# S7CAS-PLEIADES-CARTE-MERE_P07_FPGA_0.net
KiCad netlist of a schematic drawn in Altium Designer
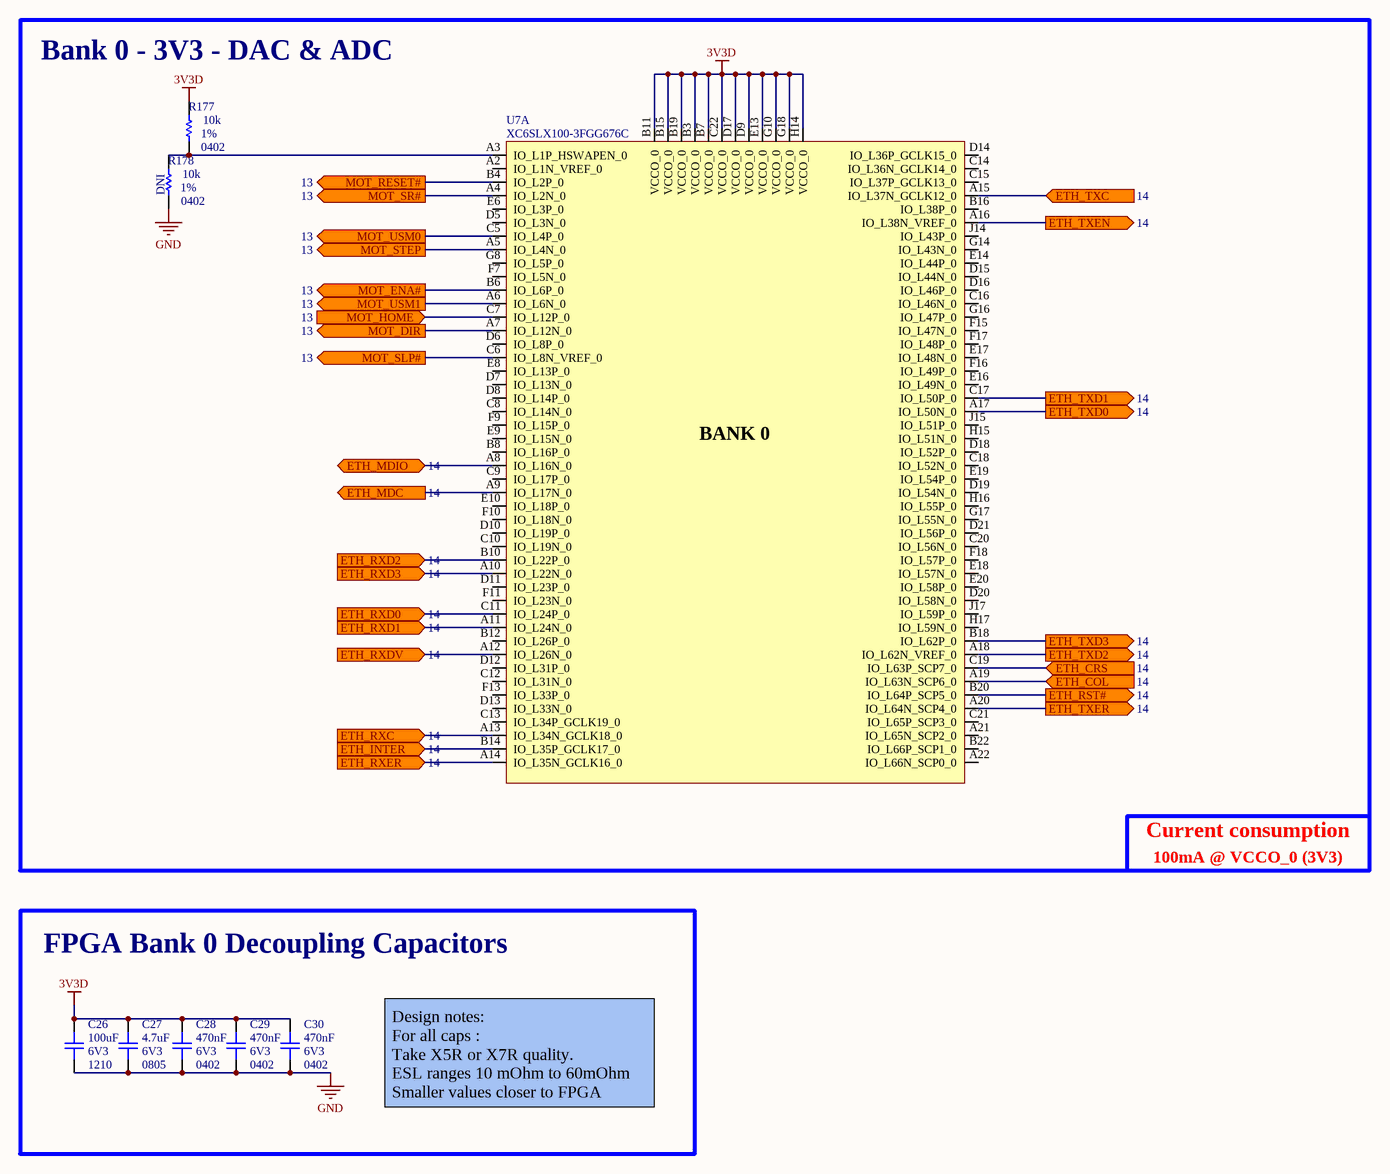
[diagram p0: S7CAS-PLEIADES-CARTE-MERE_P07_FPGA_0.SchDoc]

(export (version "E")
  (design (tool "Eeschema 10.0.6"))
  (components
    (comp (ref "C26")
      (value "100uF")
      (footprint "CAP_1210")
      (description "CAP - 1210")
      (fields
        (field (name "VOLTAGE") "6V3")
        (field (name "PACKAGE") "1210")
        (field (name "CREATEDBY") "Jonathan Bouchard")
      )
      (libsource (lib "S7CAS_LIB2021") (part "CAP - 1210"))
    )
    (comp (ref "C27")
      (value "4.7uF")
      (footprint "CAP_0805")
      (description "CAP - 0805")
      (fields
        (field (name "VOLTAGE") "6V3")
        (field (name "PACKAGE") "0805")
        (field (name "CREATEDBY") "Jonathan Bouchard")
      )
      (libsource (lib "S7CAS_LIB2021") (part "CAP - 0805"))
    )
    (comp (ref "C28")
      (value "470nF")
      (footprint "CAP_0402")
      (description "CAP - 0402")
      (fields
        (field (name "VOLTAGE") "6V3")
        (field (name "PACKAGE") "0402")
        (field (name "CREATEDBY") "Jonathan Bouchard")
      )
      (libsource (lib "S7CAS_LIB2021") (part "CAP - 0402"))
    )
    (comp (ref "C29")
      (value "470nF")
      (footprint "CAP_0402")
      (description "CAP - 0402")
      (fields
        (field (name "VOLTAGE") "6V3")
        (field (name "PACKAGE") "0402")
        (field (name "CREATEDBY") "Jonathan Bouchard")
      )
      (libsource (lib "S7CAS_LIB2021") (part "CAP - 0402"))
    )
    (comp (ref "C30")
      (value "470nF")
      (footprint "CAP_0402")
      (description "CAP - 0402")
      (fields
        (field (name "VOLTAGE") "6V3")
        (field (name "PACKAGE") "0402")
        (field (name "CREATEDBY") "Jonathan Bouchard")
      )
      (libsource (lib "S7CAS_LIB2021") (part "CAP - 0402"))
    )
    (comp (ref "R177")
      (value "10k")
      (footprint "RES_0402")
      (description "RES - 0402")
      (fields
        (field (name "VOLTAGE") "50V")
        (field (name "POWER") "1/16W")
        (field (name "PACKAGE") "0402")
        (field (name "PRECISION") "1%")
        (field (name "CREATEDBY") "Jonathan Bouchard")
      )
      (libsource (lib "S7CAS_LIB2021") (part "RES - 0402"))
    )
    (comp (ref "R178")
      (value "10k")
      (footprint "RES_0402")
      (description "RES - 0402")
      (fields
        (field (name "VOLTAGE") "50V")
        (field (name "POWER") "1/16W")
        (field (name "NI") "DNI")
        (field (name "PACKAGE") "0402")
        (field (name "PRECISION") "1%")
        (field (name "CREATEDBY") "Jonathan Bouchard")
      )
      (libsource (lib "S7CAS_LIB2021") (part "RES - 0402"))
    )
    (comp (ref "U7")
      (value "XC6SLX100-3FGG676C")
      (footprint "FPGA_XILINX_FGG676")
      (description "FPGA - XILINX SPARTAN 6 480 I/O - BGA-676")
      (fields
        (field (name "VOLTAGE") "1.14 V ~ 1.26 V")
        (field (name "MFG") "Xilinx")
        (field (name "CREATEDBY") "Jonathan Bouchard")
      )
      (libsource (lib "S7CAS_LIB2021") (part "FPGA_XC6SLX100-3FGG676C"))
    )
  )
  (nets
    (net (code "1") (name "/ETH_COL") (class "Default")
      (node (ref "U7") (pin "A19") (pinfunction "IO_L63N_SCP6_0_A19") (pintype "passive"))
    )
    (net (code "2") (name "/ETH_CRS") (class "Default")
      (node (ref "U7") (pin "C19") (pinfunction "IO_L63P_SCP7_0_C19") (pintype "passive"))
    )
    (net (code "3") (name "/ETH_INTER") (class "Default")
      (node (ref "U7") (pin "B14") (pinfunction "IO_L35P_GCLK17_0_B14") (pintype "passive"))
    )
    (net (code "4") (name "/ETH_MDC") (class "Default")
      (node (ref "U7") (pin "A9") (pinfunction "IO_L17N_0_A9") (pintype "passive"))
    )
    (net (code "5") (name "/ETH_MDIO") (class "Default")
      (node (ref "U7") (pin "A8") (pinfunction "IO_L16N_0_A8") (pintype "passive"))
    )
    (net (code "6") (name "/ETH_RST#") (class "Default")
      (node (ref "U7") (pin "B20") (pinfunction "IO_L64P_SCP5_0_B20") (pintype "passive"))
    )
    (net (code "7") (name "/ETH_RXC") (class "Default")
      (node (ref "U7") (pin "A13") (pinfunction "IO_L34N_GCLK18_0_A13") (pintype "passive"))
    )
    (net (code "8") (name "/ETH_RXD0") (class "Default")
      (node (ref "U7") (pin "C11") (pinfunction "IO_L24P_0_C11") (pintype "passive"))
    )
    (net (code "9") (name "/ETH_RXD1") (class "Default")
      (node (ref "U7") (pin "A11") (pinfunction "IO_L24N_0_A11") (pintype "passive"))
    )
    (net (code "10") (name "/ETH_RXD2") (class "Default")
      (node (ref "U7") (pin "B10") (pinfunction "IO_L22P_0_B10") (pintype "passive"))
    )
    (net (code "11") (name "/ETH_RXD3") (class "Default")
      (node (ref "U7") (pin "A10") (pinfunction "IO_L22N_0_A10") (pintype "passive"))
    )
    (net (code "12") (name "/ETH_RXDV") (class "Default")
      (node (ref "U7") (pin "A12") (pinfunction "IO_L26N_0_A12") (pintype "passive"))
    )
    (net (code "13") (name "/ETH_RXER") (class "Default")
      (node (ref "U7") (pin "A14") (pinfunction "IO_L35N_GCLK16_0_A14") (pintype "passive"))
    )
    (net (code "14") (name "/ETH_TXC") (class "Default")
      (node (ref "U7") (pin "A15") (pinfunction "IO_L37N_GCLK12_0_A15") (pintype "passive"))
    )
    (net (code "15") (name "/ETH_TXD0") (class "Default")
      (node (ref "U7") (pin "A17") (pinfunction "IO_L50N_0_A17") (pintype "passive"))
    )
    (net (code "16") (name "/ETH_TXD1") (class "Default")
      (node (ref "U7") (pin "C17") (pinfunction "IO_L50P_0_C17") (pintype "passive"))
    )
    (net (code "17") (name "/ETH_TXD2") (class "Default")
      (node (ref "U7") (pin "A18") (pinfunction "IO_L62N_VREF_0_A18") (pintype "passive"))
    )
    (net (code "18") (name "/ETH_TXD3") (class "Default")
      (node (ref "U7") (pin "B18") (pinfunction "IO_L62P_0_B18") (pintype "passive"))
    )
    (net (code "19") (name "/ETH_TXEN") (class "Default")
      (node (ref "U7") (pin "A16") (pinfunction "IO_L38N_VREF_0_A16") (pintype "passive"))
    )
    (net (code "20") (name "/ETH_TXER") (class "Default")
      (node (ref "U7") (pin "A20") (pinfunction "IO_L64N_SCP4_0_A20") (pintype "passive"))
    )
    (net (code "21") (name "/MOT_DIR") (class "Default")
      (node (ref "U7") (pin "A7") (pinfunction "IO_L12N_0_A7") (pintype "passive"))
    )
    (net (code "22") (name "/MOT_ENA#") (class "Default")
      (node (ref "U7") (pin "B6") (pinfunction "IO_L6P_0_B6") (pintype "passive"))
    )
    (net (code "23") (name "/MOT_HOME") (class "Default")
      (node (ref "U7") (pin "C7") (pinfunction "IO_L12P_0_C7") (pintype "passive"))
    )
    (net (code "24") (name "/MOT_RESET#") (class "Default")
      (node (ref "U7") (pin "B4") (pinfunction "IO_L2P_0_B4") (pintype "passive"))
    )
    (net (code "25") (name "/MOT_SLP#") (class "Default")
      (node (ref "U7") (pin "C6") (pinfunction "IO_L8N_VREF_0_C6") (pintype "passive"))
    )
    (net (code "26") (name "/MOT_SR#") (class "Default")
      (node (ref "U7") (pin "A4") (pinfunction "IO_L2N_0_A4") (pintype "passive"))
    )
    (net (code "27") (name "/MOT_STEP") (class "Default")
      (node (ref "U7") (pin "A5") (pinfunction "IO_L4N_0_A5") (pintype "passive"))
    )
    (net (code "28") (name "/MOT_USM0") (class "Default")
      (node (ref "U7") (pin "C5") (pinfunction "IO_L4P_0_C5") (pintype "passive"))
    )
    (net (code "29") (name "/MOT_USM1") (class "Default")
      (node (ref "U7") (pin "A6") (pinfunction "IO_L6N_0_A6") (pintype "passive"))
    )
    (net (code "30") (name "3V3D") (class "Default")
      (node (ref "C26") (pin "2") (pinfunction "2_2") (pintype "passive"))
      (node (ref "C27") (pin "2") (pinfunction "2_2") (pintype "passive"))
      (node (ref "C28") (pin "2") (pinfunction "2_2") (pintype "passive"))
      (node (ref "C29") (pin "2") (pinfunction "2_2") (pintype "passive"))
      (node (ref "C30") (pin "2") (pinfunction "2_2") (pintype "passive"))
      (node (ref "R177") (pin "2") (pinfunction "2_2") (pintype "passive"))
      (node (ref "U7") (pin "B11") (pinfunction "VCCO_0_B11") (pintype "passive"))
      (node (ref "U7") (pin "B15") (pinfunction "VCCO_0_B15") (pintype "passive"))
      (node (ref "U7") (pin "B19") (pinfunction "VCCO_0_B19") (pintype "passive"))
      (node (ref "U7") (pin "B3") (pinfunction "VCCO_0_B3") (pintype "passive"))
      (node (ref "U7") (pin "B7") (pinfunction "VCCO_0_B7") (pintype "passive"))
      (node (ref "U7") (pin "C22") (pinfunction "VCCO_0_C22") (pintype "passive"))
      (node (ref "U7") (pin "D17") (pinfunction "VCCO_0_D17") (pintype "passive"))
      (node (ref "U7") (pin "D9") (pinfunction "VCCO_0_D9") (pintype "passive"))
      (node (ref "U7") (pin "E13") (pinfunction "VCCO_0_E13") (pintype "passive"))
      (node (ref "U7") (pin "G10") (pinfunction "VCCO_0_G10") (pintype "passive"))
      (node (ref "U7") (pin "G18") (pinfunction "VCCO_0_G18") (pintype "passive"))
      (node (ref "U7") (pin "H14") (pinfunction "VCCO_0_H14") (pintype "passive"))
    )
    (net (code "31") (name "GND") (class "Default")
      (node (ref "C26") (pin "1") (pinfunction "1_1") (pintype "passive"))
      (node (ref "C27") (pin "1") (pinfunction "1_1") (pintype "passive"))
      (node (ref "C28") (pin "1") (pinfunction "1_1") (pintype "passive"))
      (node (ref "C29") (pin "1") (pinfunction "1_1") (pintype "passive"))
      (node (ref "C30") (pin "1") (pinfunction "1_1") (pintype "passive"))
      (node (ref "R178") (pin "1") (pinfunction "1_1") (pintype "passive"))
    )
    (net (code "32") (name "Net-(U7A-IO_L1P_HSWAPEN_0)") (class "Default")
      (node (ref "R177") (pin "1") (pinfunction "1_1") (pintype "passive"))
      (node (ref "R178") (pin "2") (pinfunction "2_2") (pintype "passive"))
      (node (ref "U7") (pin "A3") (pinfunction "IO_L1P_HSWAPEN_0_A3") (pintype "passive"))
    )
    (net (code "33") (name "unconnected-(U7A-IO_L1N_VREF_0-PadA2)") (class "Default")
      (node (ref "U7") (pin "A2") (pinfunction "IO_L1N_VREF_0_A2") (pintype "passive"))
    )
    (net (code "34") (name "unconnected-(U7A-IO_L3N_0-PadD5)") (class "Default")
      (node (ref "U7") (pin "D5") (pinfunction "IO_L3N_0_D5") (pintype "passive"))
    )
    (net (code "35") (name "unconnected-(U7A-IO_L3P_0-PadE6)") (class "Default")
      (node (ref "U7") (pin "E6") (pinfunction "IO_L3P_0_E6") (pintype "passive"))
    )
    (net (code "36") (name "unconnected-(U7A-IO_L5N_0-PadF7)") (class "Default")
      (node (ref "U7") (pin "F7") (pinfunction "IO_L5N_0_F7") (pintype "passive"))
    )
    (net (code "37") (name "unconnected-(U7A-IO_L5P_0-PadG8)") (class "Default")
      (node (ref "U7") (pin "G8") (pinfunction "IO_L5P_0_G8") (pintype "passive"))
    )
    (net (code "38") (name "unconnected-(U7A-IO_L8P_0-PadD6)") (class "Default")
      (node (ref "U7") (pin "D6") (pinfunction "IO_L8P_0_D6") (pintype "passive"))
    )
    (net (code "39") (name "unconnected-(U7A-IO_L13N_0-PadD7)") (class "Default")
      (node (ref "U7") (pin "D7") (pinfunction "IO_L13N_0_D7") (pintype "passive"))
    )
    (net (code "40") (name "unconnected-(U7A-IO_L13P_0-PadE8)") (class "Default")
      (node (ref "U7") (pin "E8") (pinfunction "IO_L13P_0_E8") (pintype "passive"))
    )
    (net (code "41") (name "unconnected-(U7A-IO_L14N_0-PadC8)") (class "Default")
      (node (ref "U7") (pin "C8") (pinfunction "IO_L14N_0_C8") (pintype "passive"))
    )
    (net (code "42") (name "unconnected-(U7A-IO_L14P_0-PadD8)") (class "Default")
      (node (ref "U7") (pin "D8") (pinfunction "IO_L14P_0_D8") (pintype "passive"))
    )
    (net (code "43") (name "unconnected-(U7A-IO_L15N_0-PadE9)") (class "Default")
      (node (ref "U7") (pin "E9") (pinfunction "IO_L15N_0_E9") (pintype "passive"))
    )
    (net (code "44") (name "unconnected-(U7A-IO_L15P_0-PadF9)") (class "Default")
      (node (ref "U7") (pin "F9") (pinfunction "IO_L15P_0_F9") (pintype "passive"))
    )
    (net (code "45") (name "unconnected-(U7A-IO_L16P_0-PadB8)") (class "Default")
      (node (ref "U7") (pin "B8") (pinfunction "IO_L16P_0_B8") (pintype "passive"))
    )
    (net (code "46") (name "unconnected-(U7A-IO_L17P_0-PadC9)") (class "Default")
      (node (ref "U7") (pin "C9") (pinfunction "IO_L17P_0_C9") (pintype "passive"))
    )
    (net (code "47") (name "unconnected-(U7A-IO_L18N_0-PadF10)") (class "Default")
      (node (ref "U7") (pin "F10") (pinfunction "IO_L18N_0_F10") (pintype "passive"))
    )
    (net (code "48") (name "unconnected-(U7A-IO_L18P_0-PadE10)") (class "Default")
      (node (ref "U7") (pin "E10") (pinfunction "IO_L18P_0_E10") (pintype "passive"))
    )
    (net (code "49") (name "unconnected-(U7A-IO_L19N_0-PadC10)") (class "Default")
      (node (ref "U7") (pin "C10") (pinfunction "IO_L19N_0_C10") (pintype "passive"))
    )
    (net (code "50") (name "unconnected-(U7A-IO_L19P_0-PadD10)") (class "Default")
      (node (ref "U7") (pin "D10") (pinfunction "IO_L19P_0_D10") (pintype "passive"))
    )
    (net (code "51") (name "unconnected-(U7A-IO_L23N_0-PadF11)") (class "Default")
      (node (ref "U7") (pin "F11") (pinfunction "IO_L23N_0_F11") (pintype "passive"))
    )
    (net (code "52") (name "unconnected-(U7A-IO_L23P_0-PadD11)") (class "Default")
      (node (ref "U7") (pin "D11") (pinfunction "IO_L23P_0_D11") (pintype "passive"))
    )
    (net (code "53") (name "unconnected-(U7A-IO_L26P_0-PadB12)") (class "Default")
      (node (ref "U7") (pin "B12") (pinfunction "IO_L26P_0_B12") (pintype "passive"))
    )
    (net (code "54") (name "unconnected-(U7A-IO_L31N_0-PadC12)") (class "Default")
      (node (ref "U7") (pin "C12") (pinfunction "IO_L31N_0_C12") (pintype "passive"))
    )
    (net (code "55") (name "unconnected-(U7A-IO_L31P_0-PadD12)") (class "Default")
      (node (ref "U7") (pin "D12") (pinfunction "IO_L31P_0_D12") (pintype "passive"))
    )
    (net (code "56") (name "unconnected-(U7A-IO_L33N_0-PadD13)") (class "Default")
      (node (ref "U7") (pin "D13") (pinfunction "IO_L33N_0_D13") (pintype "passive"))
    )
    (net (code "57") (name "unconnected-(U7A-IO_L33P_0-PadF13)") (class "Default")
      (node (ref "U7") (pin "F13") (pinfunction "IO_L33P_0_F13") (pintype "passive"))
    )
    (net (code "58") (name "unconnected-(U7A-IO_L34P_GCLK19_0-PadC13)") (class "Default")
      (node (ref "U7") (pin "C13") (pinfunction "IO_L34P_GCLK19_0_C13") (pintype "passive"))
    )
    (net (code "59") (name "unconnected-(U7A-IO_L36N_GCLK14_0-PadC14)") (class "Default")
      (node (ref "U7") (pin "C14") (pinfunction "IO_L36N_GCLK14_0_C14") (pintype "passive"))
    )
    (net (code "60") (name "unconnected-(U7A-IO_L36P_GCLK15_0-PadD14)") (class "Default")
      (node (ref "U7") (pin "D14") (pinfunction "IO_L36P_GCLK15_0_D14") (pintype "passive"))
    )
    (net (code "61") (name "unconnected-(U7A-IO_L37P_GCLK13_0-PadC15)") (class "Default")
      (node (ref "U7") (pin "C15") (pinfunction "IO_L37P_GCLK13_0_C15") (pintype "passive"))
    )
    (net (code "62") (name "unconnected-(U7A-IO_L38P_0-PadB16)") (class "Default")
      (node (ref "U7") (pin "B16") (pinfunction "IO_L38P_0_B16") (pintype "passive"))
    )
    (net (code "63") (name "unconnected-(U7A-IO_L43N_0-PadG14)") (class "Default")
      (node (ref "U7") (pin "G14") (pinfunction "IO_L43N_0_G14") (pintype "passive"))
    )
    (net (code "64") (name "unconnected-(U7A-IO_L43P_0-PadJ14)") (class "Default")
      (node (ref "U7") (pin "J14") (pinfunction "IO_L43P_0_J14") (pintype "passive"))
    )
    (net (code "65") (name "unconnected-(U7A-IO_L44N_0-PadD15)") (class "Default")
      (node (ref "U7") (pin "D15") (pinfunction "IO_L44N_0_D15") (pintype "passive"))
    )
    (net (code "66") (name "unconnected-(U7A-IO_L44P_0-PadE14)") (class "Default")
      (node (ref "U7") (pin "E14") (pinfunction "IO_L44P_0_E14") (pintype "passive"))
    )
    (net (code "67") (name "unconnected-(U7A-IO_L46N_0-PadC16)") (class "Default")
      (node (ref "U7") (pin "C16") (pinfunction "IO_L46N_0_C16") (pintype "passive"))
    )
    (net (code "68") (name "unconnected-(U7A-IO_L46P_0-PadD16)") (class "Default")
      (node (ref "U7") (pin "D16") (pinfunction "IO_L46P_0_D16") (pintype "passive"))
    )
    (net (code "69") (name "unconnected-(U7A-IO_L47N_0-PadF15)") (class "Default")
      (node (ref "U7") (pin "F15") (pinfunction "IO_L47N_0_F15") (pintype "passive"))
    )
    (net (code "70") (name "unconnected-(U7A-IO_L47P_0-PadG16)") (class "Default")
      (node (ref "U7") (pin "G16") (pinfunction "IO_L47P_0_G16") (pintype "passive"))
    )
    (net (code "71") (name "unconnected-(U7A-IO_L48N_0-PadE17)") (class "Default")
      (node (ref "U7") (pin "E17") (pinfunction "IO_L48N_0_E17") (pintype "passive"))
    )
    (net (code "72") (name "unconnected-(U7A-IO_L48P_0-PadF17)") (class "Default")
      (node (ref "U7") (pin "F17") (pinfunction "IO_L48P_0_F17") (pintype "passive"))
    )
    (net (code "73") (name "unconnected-(U7A-IO_L49N_0-PadE16)") (class "Default")
      (node (ref "U7") (pin "E16") (pinfunction "IO_L49N_0_E16") (pintype "passive"))
    )
    (net (code "74") (name "unconnected-(U7A-IO_L49P_0-PadF16)") (class "Default")
      (node (ref "U7") (pin "F16") (pinfunction "IO_L49P_0_F16") (pintype "passive"))
    )
    (net (code "75") (name "unconnected-(U7A-IO_L51N_0-PadH15)") (class "Default")
      (node (ref "U7") (pin "H15") (pinfunction "IO_L51N_0_H15") (pintype "passive"))
    )
    (net (code "76") (name "unconnected-(U7A-IO_L51P_0-PadJ15)") (class "Default")
      (node (ref "U7") (pin "J15") (pinfunction "IO_L51P_0_J15") (pintype "passive"))
    )
    (net (code "77") (name "unconnected-(U7A-IO_L52N_0-PadC18)") (class "Default")
      (node (ref "U7") (pin "C18") (pinfunction "IO_L52N_0_C18") (pintype "passive"))
    )
    (net (code "78") (name "unconnected-(U7A-IO_L52P_0-PadD18)") (class "Default")
      (node (ref "U7") (pin "D18") (pinfunction "IO_L52P_0_D18") (pintype "passive"))
    )
    (net (code "79") (name "unconnected-(U7A-IO_L54N_0-PadD19)") (class "Default")
      (node (ref "U7") (pin "D19") (pinfunction "IO_L54N_0_D19") (pintype "passive"))
    )
    (net (code "80") (name "unconnected-(U7A-IO_L54P_0-PadE19)") (class "Default")
      (node (ref "U7") (pin "E19") (pinfunction "IO_L54P_0_E19") (pintype "passive"))
    )
    (net (code "81") (name "unconnected-(U7A-IO_L55N_0-PadG17)") (class "Default")
      (node (ref "U7") (pin "G17") (pinfunction "IO_L55N_0_G17") (pintype "passive"))
    )
    (net (code "82") (name "unconnected-(U7A-IO_L55P_0-PadH16)") (class "Default")
      (node (ref "U7") (pin "H16") (pinfunction "IO_L55P_0_H16") (pintype "passive"))
    )
    (net (code "83") (name "unconnected-(U7A-IO_L56N_0-PadC20)") (class "Default")
      (node (ref "U7") (pin "C20") (pinfunction "IO_L56N_0_C20") (pintype "passive"))
    )
    (net (code "84") (name "unconnected-(U7A-IO_L56P_0-PadD21)") (class "Default")
      (node (ref "U7") (pin "D21") (pinfunction "IO_L56P_0_D21") (pintype "passive"))
    )
    (net (code "85") (name "unconnected-(U7A-IO_L57N_0-PadE18)") (class "Default")
      (node (ref "U7") (pin "E18") (pinfunction "IO_L57N_0_E18") (pintype "passive"))
    )
    (net (code "86") (name "unconnected-(U7A-IO_L57P_0-PadF18)") (class "Default")
      (node (ref "U7") (pin "F18") (pinfunction "IO_L57P_0_F18") (pintype "passive"))
    )
    (net (code "87") (name "unconnected-(U7A-IO_L58N_0-PadD20)") (class "Default")
      (node (ref "U7") (pin "D20") (pinfunction "IO_L58N_0_D20") (pintype "passive"))
    )
    (net (code "88") (name "unconnected-(U7A-IO_L58P_0-PadE20)") (class "Default")
      (node (ref "U7") (pin "E20") (pinfunction "IO_L58P_0_E20") (pintype "passive"))
    )
    (net (code "89") (name "unconnected-(U7A-IO_L59N_0-PadH17)") (class "Default")
      (node (ref "U7") (pin "H17") (pinfunction "IO_L59N_0_H17") (pintype "passive"))
    )
    (net (code "90") (name "unconnected-(U7A-IO_L59P_0-PadJ17)") (class "Default")
      (node (ref "U7") (pin "J17") (pinfunction "IO_L59P_0_J17") (pintype "passive"))
    )
    (net (code "91") (name "unconnected-(U7A-IO_L65N_SCP2_0-PadA21)") (class "Default")
      (node (ref "U7") (pin "A21") (pinfunction "IO_L65N_SCP2_0_A21") (pintype "passive"))
    )
    (net (code "92") (name "unconnected-(U7A-IO_L65P_SCP3_0-PadC21)") (class "Default")
      (node (ref "U7") (pin "C21") (pinfunction "IO_L65P_SCP3_0_C21") (pintype "passive"))
    )
    (net (code "93") (name "unconnected-(U7A-IO_L66N_SCP0_0-PadA22)") (class "Default")
      (node (ref "U7") (pin "A22") (pinfunction "IO_L66N_SCP0_0_A22") (pintype "passive"))
    )
    (net (code "94") (name "unconnected-(U7A-IO_L66P_SCP1_0-PadB22)") (class "Default")
      (node (ref "U7") (pin "B22") (pinfunction "IO_L66P_SCP1_0_B22") (pintype "passive"))
    )
  )
)
